# 09_SERIAL_PORT.net
KiCad netlist of a schematic drawn in Altium Designer
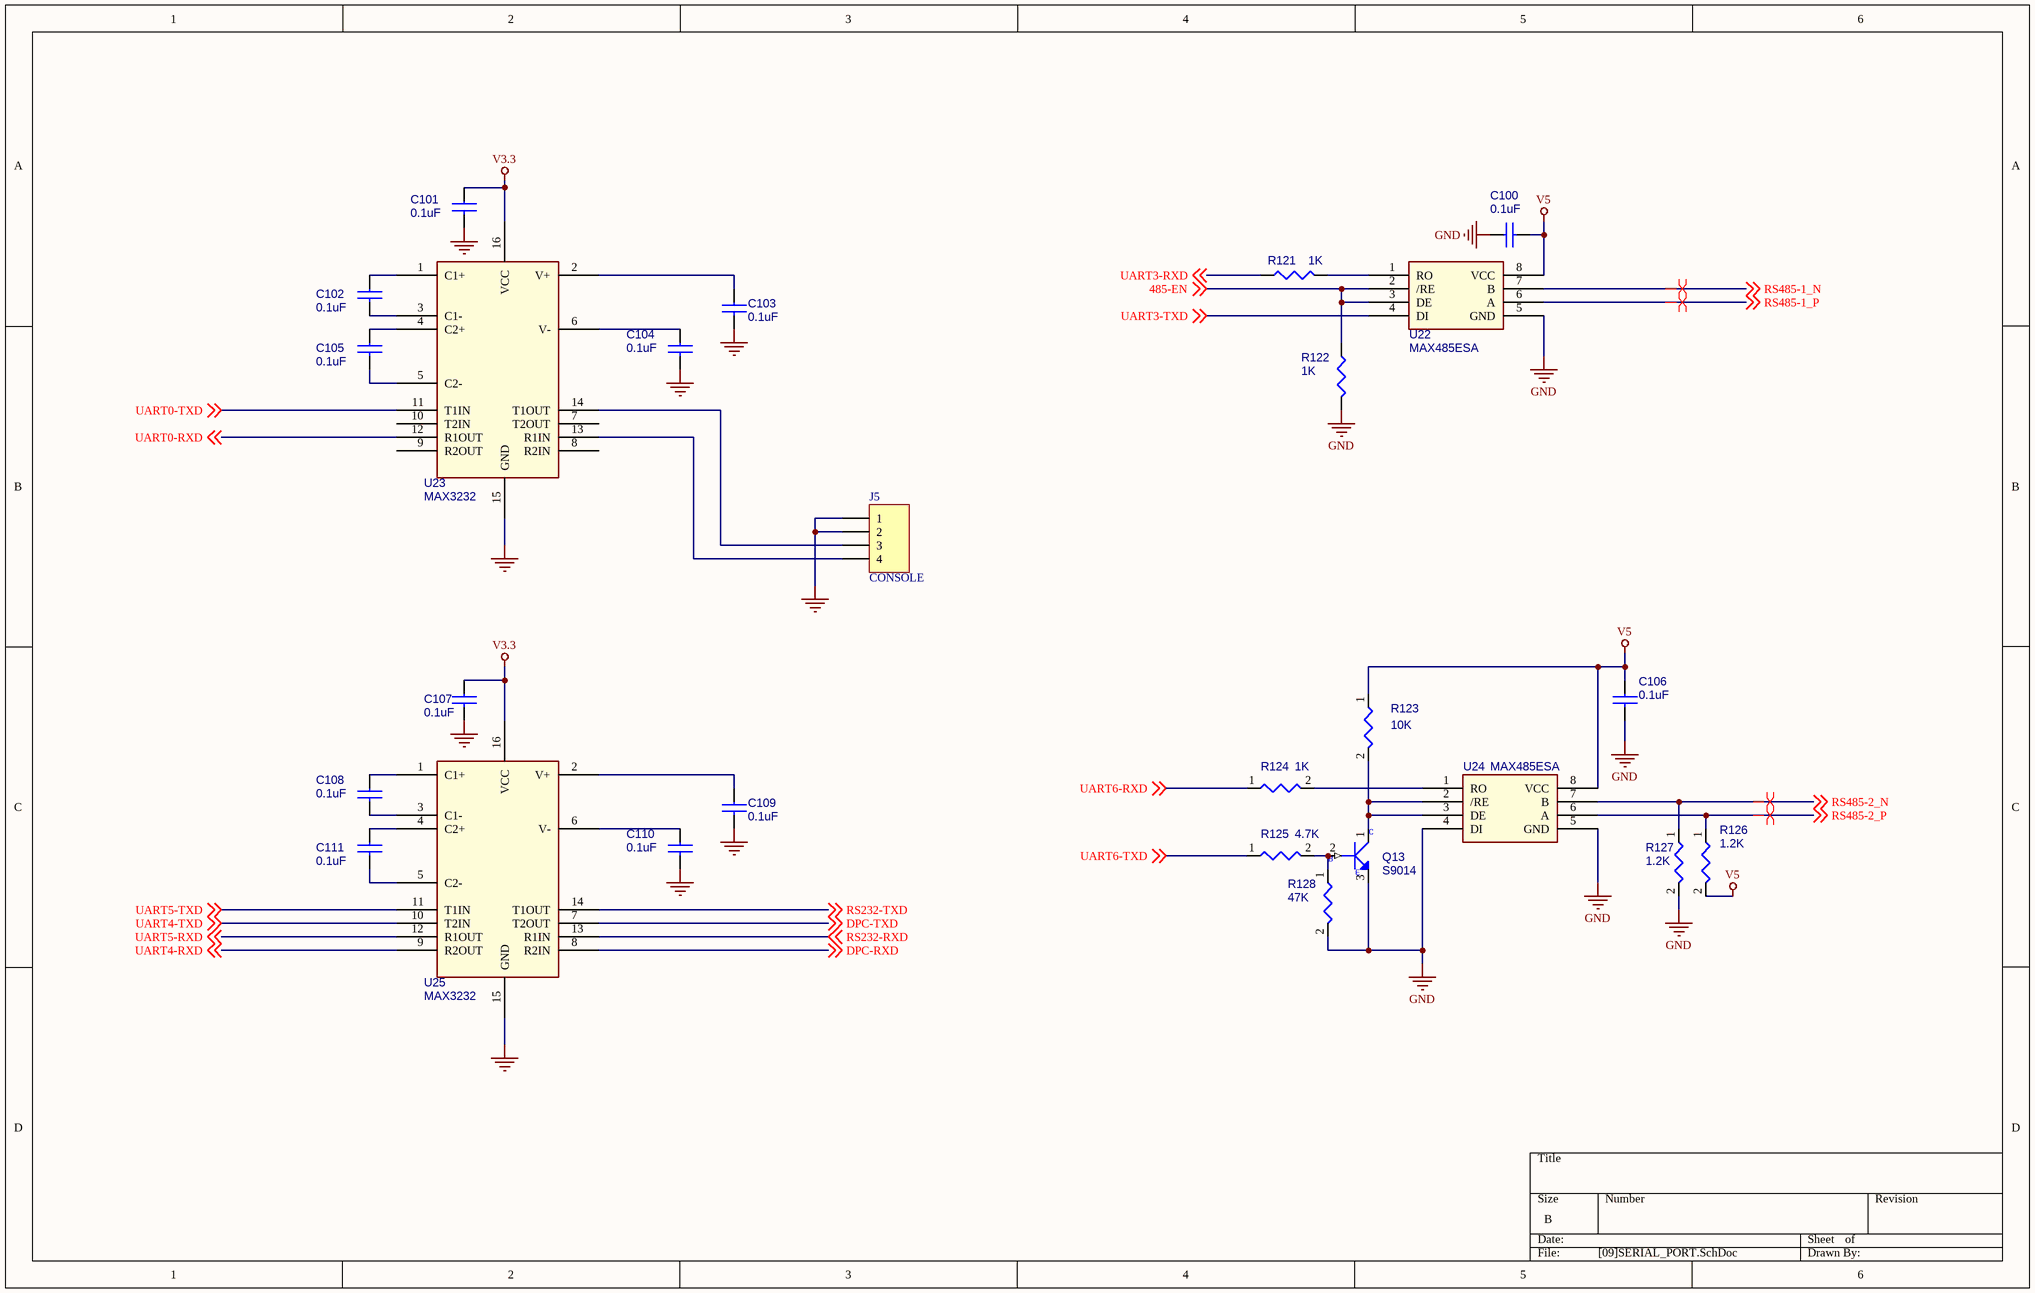
[diagram p0: [09]SERIAL_PORT.SchDoc]

(export (version "E")
  (design (tool "Eeschema 10.0.6"))
  (components
    (comp (ref "C100")
      (value "0.1uF")
      (fields (field (name "PART NUMBER") "SE132225K8L"))
      (libsource (lib "*") (part "P_CAP NP"))
    )
    (comp (ref "C101") (value "0.1uF") (libsource (lib "*") (part "CAP")))
    (comp (ref "C102") (value "0.1uF") (libsource (lib "*") (part "CAP")))
    (comp (ref "C103") (value "0.1uF") (libsource (lib "*") (part "CAP")))
    (comp (ref "C104") (value "0.1uF") (libsource (lib "*") (part "CAP")))
    (comp (ref "C105") (value "0.1uF") (libsource (lib "*") (part "CAP")))
    (comp (ref "C106") (value "0.1uF") (libsource (lib "*") (part "CAP")))
    (comp (ref "C107") (value "0.1uF") (libsource (lib "*") (part "CAP")))
    (comp (ref "C108") (value "0.1uF") (libsource (lib "*") (part "CAP")))
    (comp (ref "C109") (value "0.1uF") (libsource (lib "*") (part "CAP")))
    (comp (ref "C110") (value "0.1uF") (libsource (lib "*") (part "CAP")))
    (comp (ref "C111") (value "0.1uF") (libsource (lib "*") (part "CAP")))
    (comp (ref "J5")
      (value "CONSOLE")
      (footprint "HDR2X2H")
      (description "Header, 4-Pin")
      (libsource (lib "Miscellaneous Connectors") (part "Header 4"))
    )
    (comp (ref "Q13")
      (value "S9014")
      (footprint "NPN")
      (fields (field (name "PART NUMBER") "SB039040000"))
      (libsource (lib "*") (part "MMBT3904_NL_SOT23-3"))
    )
    (comp (ref "R121")
      (value "1K")
      (fields (field (name "PART NUMBER") "SD02810028L"))
      (libsource (lib "") (part "R_1"))
    )
    (comp (ref "R122")
      (value "1K")
      (fields (field (name "PART NUMBER") "SD02810028L"))
      (libsource (lib "") (part "R_1"))
    )
    (comp (ref "R123")
      (value "10K")
      (fields (field (name "PART NUMBER") "SD02810028L"))
      (libsource (lib "*") (part "R"))
    )
    (comp (ref "R124")
      (value "1K")
      (fields (field (name "PART NUMBER") "SD02810028L"))
      (libsource (lib "*") (part "R"))
    )
    (comp (ref "R125")
      (value "4.7K")
      (fields (field (name "PART NUMBER") "SD02810028L"))
      (libsource (lib "*") (part "R"))
    )
    (comp (ref "R126")
      (value "1.2K")
      (fields (field (name "PART NUMBER") "SD02810028L"))
      (libsource (lib "*") (part "R"))
    )
    (comp (ref "R127")
      (value "1.2K")
      (fields (field (name "PART NUMBER") "SD02810028L"))
      (libsource (lib "*") (part "R"))
    )
    (comp (ref "R128")
      (value "47K")
      (fields (field (name "PART NUMBER") "SD02810028L"))
      (libsource (lib "*") (part "R"))
    )
    (comp (ref "U22") (value "MAX485ESA") (libsource (lib "*") (part "MAX485")))
    (comp (ref "U23") (value "MAX3232") (footprint "SO-16") (libsource (lib "*") (part "MAX3232")))
    (comp (ref "U24") (value "MAX485ESA") (libsource (lib "*") (part "MAX485")))
    (comp (ref "U25") (value "MAX3232") (footprint "SO-16") (libsource (lib "*") (part "MAX3232")))
  )
  (nets
    (net (code "1") (name "485-EN") (class "Default")
      (node (ref "R122") (pin "1") (pinfunction "1_1") (pintype "passive"))
      (node (ref "U22") (pin "2") (pinfunction "/RE_2") (pintype "passive"))
      (node (ref "U22") (pin "3") (pinfunction "DE_3") (pintype "passive"))
    )
    (net (code "2") (name "DPC-RXD") (class "Default")
      (node (ref "U25") (pin "8") (pinfunction "R2IN_8") (pintype "passive"))
    )
    (net (code "3") (name "DPC-TXD") (class "Default")
      (node (ref "U25") (pin "7") (pinfunction "T2OUT_7") (pintype "passive"))
    )
    (net (code "4") (name "GND") (class "Default")
      (node (ref "C100") (pin "1") (pinfunction "1_1") (pintype "passive"))
      (node (ref "C101") (pin "2") (pinfunction "2_2") (pintype "passive"))
      (node (ref "C103") (pin "2") (pinfunction "2_2") (pintype "passive"))
      (node (ref "C104") (pin "2") (pinfunction "2_2") (pintype "passive"))
      (node (ref "C106") (pin "2") (pinfunction "2_2") (pintype "passive"))
      (node (ref "C107") (pin "2") (pinfunction "2_2") (pintype "passive"))
      (node (ref "C109") (pin "2") (pinfunction "2_2") (pintype "passive"))
      (node (ref "C110") (pin "2") (pinfunction "2_2") (pintype "passive"))
      (node (ref "J5") (pin "1") (pinfunction "1_1") (pintype "passive"))
      (node (ref "J5") (pin "2") (pinfunction "2_2") (pintype "passive"))
      (node (ref "Q13") (pin "3") (pinfunction "EMITTER_3") (pintype "passive"))
      (node (ref "R122") (pin "2") (pinfunction "2_2") (pintype "passive"))
      (node (ref "R127") (pin "2") (pinfunction "2_2") (pintype "passive"))
      (node (ref "R128") (pin "2") (pinfunction "2_2") (pintype "passive"))
      (node (ref "U22") (pin "5") (pinfunction "GND_5") (pintype "passive"))
      (node (ref "U23") (pin "15") (pinfunction "GND_15") (pintype "passive"))
      (node (ref "U24") (pin "4") (pinfunction "DI_4") (pintype "passive"))
      (node (ref "U24") (pin "5") (pinfunction "GND_5") (pintype "passive"))
      (node (ref "U25") (pin "15") (pinfunction "GND_15") (pintype "passive"))
    )
    (net (code "5") (name "Net-(Q13-BASE)") (class "Default")
      (node (ref "Q13") (pin "2") (pinfunction "BASE_2") (pintype "input"))
      (node (ref "R125") (pin "2") (pinfunction "2_2") (pintype "passive"))
      (node (ref "R128") (pin "1") (pinfunction "1_1") (pintype "passive"))
    )
    (net (code "6") (name "Net-(Q13-COLLECTOR)") (class "Default")
      (node (ref "Q13") (pin "1") (pinfunction "COLLECTOR_1") (pintype "passive"))
      (node (ref "R123") (pin "2") (pinfunction "2_2") (pintype "passive"))
      (node (ref "U24") (pin "2") (pinfunction "/RE_2") (pintype "passive"))
      (node (ref "U24") (pin "3") (pinfunction "DE_3") (pintype "passive"))
    )
    (net (code "7") (name "Net-(U22-RO)") (class "Default")
      (node (ref "R121") (pin "2") (pinfunction "2_2") (pintype "passive"))
      (node (ref "U22") (pin "1") (pinfunction "RO_1") (pintype "passive"))
    )
    (net (code "8") (name "Net-(U23-C1+)") (class "Default")
      (node (ref "C102") (pin "1") (pinfunction "1_1") (pintype "passive"))
      (node (ref "U23") (pin "1") (pinfunction "C1+_1") (pintype "passive"))
    )
    (net (code "9") (name "Net-(U23-C1-)") (class "Default")
      (node (ref "C102") (pin "2") (pinfunction "2_2") (pintype "passive"))
      (node (ref "U23") (pin "3") (pinfunction "C1-_3") (pintype "passive"))
    )
    (net (code "10") (name "Net-(U23-C2+)") (class "Default")
      (node (ref "C105") (pin "1") (pinfunction "1_1") (pintype "passive"))
      (node (ref "U23") (pin "4") (pinfunction "C2+_4") (pintype "passive"))
    )
    (net (code "11") (name "Net-(U23-C2-)") (class "Default")
      (node (ref "C105") (pin "2") (pinfunction "2_2") (pintype "passive"))
      (node (ref "U23") (pin "5") (pinfunction "C2-_5") (pintype "passive"))
    )
    (net (code "12") (name "Net-(U23-R1IN)") (class "Default")
      (node (ref "J5") (pin "4") (pinfunction "4_4") (pintype "passive"))
      (node (ref "U23") (pin "13") (pinfunction "R1IN_13") (pintype "passive"))
    )
    (net (code "13") (name "Net-(U23-T1OUT)") (class "Default")
      (node (ref "J5") (pin "3") (pinfunction "3_3") (pintype "passive"))
      (node (ref "U23") (pin "14") (pinfunction "T1OUT_14") (pintype "passive"))
    )
    (net (code "14") (name "Net-(U23-V+)") (class "Default")
      (node (ref "C103") (pin "1") (pinfunction "1_1") (pintype "passive"))
      (node (ref "U23") (pin "2") (pinfunction "V+_2") (pintype "passive"))
    )
    (net (code "15") (name "Net-(U23-V-)") (class "Default")
      (node (ref "C104") (pin "1") (pinfunction "1_1") (pintype "passive"))
      (node (ref "U23") (pin "6") (pinfunction "V-_6") (pintype "passive"))
    )
    (net (code "16") (name "Net-(U24-RO)") (class "Default")
      (node (ref "R124") (pin "2") (pinfunction "2_2") (pintype "passive"))
      (node (ref "U24") (pin "1") (pinfunction "RO_1") (pintype "passive"))
    )
    (net (code "17") (name "Net-(U25-C1+)") (class "Default")
      (node (ref "C108") (pin "1") (pinfunction "1_1") (pintype "passive"))
      (node (ref "U25") (pin "1") (pinfunction "C1+_1") (pintype "passive"))
    )
    (net (code "18") (name "Net-(U25-C1-)") (class "Default")
      (node (ref "C108") (pin "2") (pinfunction "2_2") (pintype "passive"))
      (node (ref "U25") (pin "3") (pinfunction "C1-_3") (pintype "passive"))
    )
    (net (code "19") (name "Net-(U25-C2+)") (class "Default")
      (node (ref "C111") (pin "1") (pinfunction "1_1") (pintype "passive"))
      (node (ref "U25") (pin "4") (pinfunction "C2+_4") (pintype "passive"))
    )
    (net (code "20") (name "Net-(U25-C2-)") (class "Default")
      (node (ref "C111") (pin "2") (pinfunction "2_2") (pintype "passive"))
      (node (ref "U25") (pin "5") (pinfunction "C2-_5") (pintype "passive"))
    )
    (net (code "21") (name "Net-(U25-V+)") (class "Default")
      (node (ref "C109") (pin "1") (pinfunction "1_1") (pintype "passive"))
      (node (ref "U25") (pin "2") (pinfunction "V+_2") (pintype "passive"))
    )
    (net (code "22") (name "Net-(U25-V-)") (class "Default")
      (node (ref "C110") (pin "1") (pinfunction "1_1") (pintype "passive"))
      (node (ref "U25") (pin "6") (pinfunction "V-_6") (pintype "passive"))
    )
    (net (code "23") (name "RS232-RXD") (class "Default")
      (node (ref "U25") (pin "13") (pinfunction "R1IN_13") (pintype "passive"))
    )
    (net (code "24") (name "RS232-TXD") (class "Default")
      (node (ref "U25") (pin "14") (pinfunction "T1OUT_14") (pintype "passive"))
    )
    (net (code "25") (name "RS485-1_N") (class "Default")
      (node (ref "U22") (pin "7") (pinfunction "B_7") (pintype "passive"))
    )
    (net (code "26") (name "RS485-1_P") (class "Default")
      (node (ref "U22") (pin "6") (pinfunction "A_6") (pintype "passive"))
    )
    (net (code "27") (name "RS485-2_N") (class "Default")
      (node (ref "R127") (pin "1") (pinfunction "1_1") (pintype "passive"))
      (node (ref "U24") (pin "7") (pinfunction "B_7") (pintype "passive"))
    )
    (net (code "28") (name "RS485-2_P") (class "Default")
      (node (ref "R126") (pin "1") (pinfunction "1_1") (pintype "passive"))
      (node (ref "U24") (pin "6") (pinfunction "A_6") (pintype "passive"))
    )
    (net (code "29") (name "UART0-RXD") (class "Default")
      (node (ref "U23") (pin "12") (pinfunction "R1OUT_12") (pintype "passive"))
    )
    (net (code "30") (name "UART0-TXD") (class "Default")
      (node (ref "U23") (pin "11") (pinfunction "T1IN_11") (pintype "passive"))
    )
    (net (code "31") (name "UART3-RXD") (class "Default")
      (node (ref "R121") (pin "1") (pinfunction "1_1") (pintype "passive"))
    )
    (net (code "32") (name "UART3-TXD") (class "Default")
      (node (ref "U22") (pin "4") (pinfunction "DI_4") (pintype "passive"))
    )
    (net (code "33") (name "UART4-RXD") (class "Default")
      (node (ref "U25") (pin "9") (pinfunction "R2OUT_9") (pintype "passive"))
    )
    (net (code "34") (name "UART4-TXD") (class "Default")
      (node (ref "U25") (pin "10") (pinfunction "T2IN_10") (pintype "passive"))
    )
    (net (code "35") (name "UART5-RXD") (class "Default")
      (node (ref "U25") (pin "12") (pinfunction "R1OUT_12") (pintype "passive"))
    )
    (net (code "36") (name "UART5-TXD") (class "Default")
      (node (ref "U25") (pin "11") (pinfunction "T1IN_11") (pintype "passive"))
    )
    (net (code "37") (name "UART6-RXD") (class "Default")
      (node (ref "R124") (pin "1") (pinfunction "1_1") (pintype "passive"))
    )
    (net (code "38") (name "UART6-TXD") (class "Default")
      (node (ref "R125") (pin "1") (pinfunction "1_1") (pintype "passive"))
    )
    (net (code "39") (name "V3.3") (class "Default")
      (node (ref "C101") (pin "1") (pinfunction "1_1") (pintype "passive"))
      (node (ref "C107") (pin "1") (pinfunction "1_1") (pintype "passive"))
      (node (ref "U23") (pin "16") (pinfunction "VCC_16") (pintype "passive"))
      (node (ref "U25") (pin "16") (pinfunction "VCC_16") (pintype "passive"))
    )
    (net (code "40") (name "V5") (class "Default")
      (node (ref "C100") (pin "2") (pinfunction "2_2") (pintype "passive"))
      (node (ref "C106") (pin "1") (pinfunction "1_1") (pintype "passive"))
      (node (ref "R123") (pin "1") (pinfunction "1_1") (pintype "passive"))
      (node (ref "R126") (pin "2") (pinfunction "2_2") (pintype "passive"))
      (node (ref "U22") (pin "8") (pinfunction "VCC_8") (pintype "passive"))
      (node (ref "U24") (pin "8") (pinfunction "VCC_8") (pintype "passive"))
    )
    (net (code "41") (name "unconnected-(U23-R2IN-Pad8)") (class "Default")
      (node (ref "U23") (pin "8") (pinfunction "R2IN_8") (pintype "passive"))
    )
    (net (code "42") (name "unconnected-(U23-R2OUT-Pad9)") (class "Default")
      (node (ref "U23") (pin "9") (pinfunction "R2OUT_9") (pintype "passive"))
    )
    (net (code "43") (name "unconnected-(U23-T2IN-Pad10)") (class "Default")
      (node (ref "U23") (pin "10") (pinfunction "T2IN_10") (pintype "passive"))
    )
    (net (code "44") (name "unconnected-(U23-T2OUT-Pad7)") (class "Default")
      (node (ref "U23") (pin "7") (pinfunction "T2OUT_7") (pintype "passive"))
    )
  )
)
